# Switch_de_potencia.net
KiCad netlist of a schematic drawn in EAGLE
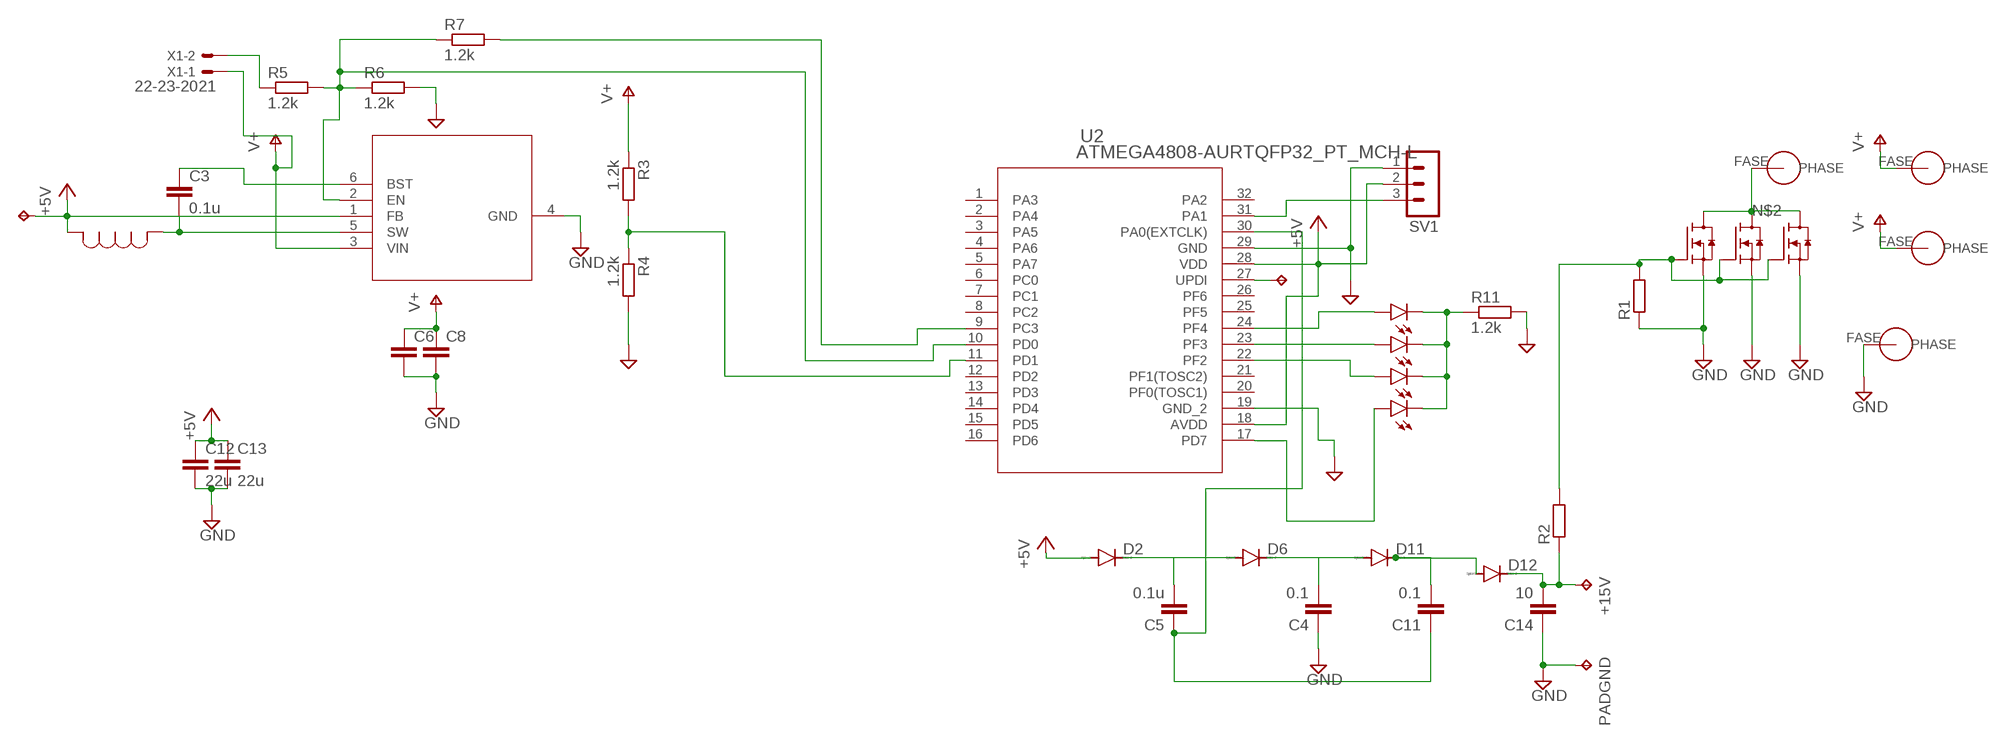
[diagram p0: schematic, sheet 1]

(export (version "E")
  (design (tool "Eeschema 10.0.6"))
  (components
    (comp (ref "+15V")
      (value "TPB1,27")
      (footprint "eagle-import:B1,27")
      (libsource (lib "eagle-import") (part "TPB1,27"))
    )
    (comp (ref "C3")
      (value "0.1u")
      (footprint "eagle-import:C0402")
      (libsource (lib "eagle-import") (part "C-EUC0402"))
    )
    (comp (ref "C4")
      (value "0.1")
      (footprint "eagle-import:C0805")
      (libsource (lib "eagle-import") (part "C-EUC0805"))
    )
    (comp (ref "C5")
      (value "0.1u")
      (footprint "eagle-import:C0805")
      (libsource (lib "eagle-import") (part "C-EUC0805"))
    )
    (comp (ref "C6")
      (value "C-EUC0805")
      (footprint "eagle-import:C0805")
      (libsource (lib "eagle-import") (part "C-EUC0805"))
    )
    (comp (ref "C8")
      (value "C-EUC0805")
      (footprint "eagle-import:C0805")
      (libsource (lib "eagle-import") (part "C-EUC0805"))
    )
    (comp (ref "C11")
      (value "0.1")
      (footprint "eagle-import:C0805")
      (libsource (lib "eagle-import") (part "C-EUC0805"))
    )
    (comp (ref "C12")
      (value "22u")
      (footprint "eagle-import:C0402")
      (libsource (lib "eagle-import") (part "C-EUC0402"))
    )
    (comp (ref "C13")
      (value "22u")
      (footprint "eagle-import:C0402")
      (libsource (lib "eagle-import") (part "C-EUC0402"))
    )
    (comp (ref "C14")
      (value "10")
      (footprint "eagle-import:C0805")
      (libsource (lib "eagle-import") (part "C-EUC0805"))
    )
    (comp (ref "D2")
      (value "DIODE-MINIMELF")
      (footprint "eagle-import:MINIMELF")
      (libsource (lib "eagle-import") (part "DIODE-MINIMELF"))
    )
    (comp (ref "D6")
      (value "DIODE-MINIMELF")
      (footprint "eagle-import:MINIMELF")
      (libsource (lib "eagle-import") (part "DIODE-MINIMELF"))
    )
    (comp (ref "D11")
      (value "DIODE-MINIMELF")
      (footprint "eagle-import:MINIMELF")
      (libsource (lib "eagle-import") (part "DIODE-MINIMELF"))
    )
    (comp (ref "D12")
      (value "DIODE-MINIMELF")
      (footprint "eagle-import:MINIMELF")
      (libsource (lib "eagle-import") (part "DIODE-MINIMELF"))
    )
    (comp (ref "GND")
      (value "PHASE")
      (footprint "eagle-import:POWEROUT")
      (libsource (lib "eagle-import") (part "PHASE"))
    )
    (comp (ref "LA1")
      (value "IPB180N06S4-H1")
      (footprint "eagle-import:PG-TO263-7-3")
      (libsource (lib "eagle-import") (part "IPB180N06S4-H1"))
    )
    (comp (ref "LA2")
      (value "IPB180N06S4-H1")
      (footprint "eagle-import:PG-TO263-7-3")
      (libsource (lib "eagle-import") (part "IPB180N06S4-H1"))
    )
    (comp (ref "LA3")
      (value "IPB180N06S4-H1")
      (footprint "eagle-import:PG-TO263-7-3")
      (libsource (lib "eagle-import") (part "IPB180N06S4-H1"))
    )
    (comp (ref "OUTPUT")
      (value "PHASE")
      (footprint "eagle-import:POWEROUT")
      (libsource (lib "eagle-import") (part "PHASE"))
    )
    (comp (ref "PADGND")
      (value "TPB1,27")
      (footprint "eagle-import:B1,27")
      (libsource (lib "eagle-import") (part "TPB1,27"))
    )
    (comp (ref "POWERON2")
      (value "LEDCHIPLED_0603")
      (footprint "eagle-import:CHIPLED_0603")
      (libsource (lib "eagle-import") (part "LEDCHIPLED_0603"))
    )
    (comp (ref "POWERON3")
      (value "LEDCHIPLED_0603")
      (footprint "eagle-import:CHIPLED_0603")
      (libsource (lib "eagle-import") (part "LEDCHIPLED_0603"))
    )
    (comp (ref "POWERON4")
      (value "LEDCHIPLED_0603")
      (footprint "eagle-import:CHIPLED_0603")
      (libsource (lib "eagle-import") (part "LEDCHIPLED_0603"))
    )
    (comp (ref "POWERON5")
      (value "LEDCHIPLED_0603")
      (footprint "eagle-import:CHIPLED_0603")
      (libsource (lib "eagle-import") (part "LEDCHIPLED_0603"))
    )
    (comp (ref "R1")
      (value "R-EU_R0603")
      (footprint "eagle-import:R0603")
      (libsource (lib "eagle-import") (part "R-EU_R0603"))
    )
    (comp (ref "R2")
      (value "R-EU_R0603")
      (footprint "eagle-import:R0603")
      (libsource (lib "eagle-import") (part "R-EU_R0603"))
    )
    (comp (ref "R3")
      (value "1.2k")
      (footprint "eagle-import:M0805")
      (libsource (lib "eagle-import") (part "R-EU_M0805"))
    )
    (comp (ref "R4")
      (value "1.2k")
      (footprint "eagle-import:M0805")
      (libsource (lib "eagle-import") (part "R-EU_M0805"))
    )
    (comp (ref "R5")
      (value "1.2k")
      (footprint "eagle-import:M0805")
      (libsource (lib "eagle-import") (part "R-EU_M0805"))
    )
    (comp (ref "R6")
      (value "1.2k")
      (footprint "eagle-import:M0805")
      (libsource (lib "eagle-import") (part "R-EU_M0805"))
    )
    (comp (ref "R7")
      (value "1.2k")
      (footprint "eagle-import:M0805")
      (libsource (lib "eagle-import") (part "R-EU_M0805"))
    )
    (comp (ref "R11")
      (value "1.2k")
      (footprint "eagle-import:M0805")
      (libsource (lib "eagle-import") (part "R-EU_M0805"))
    )
    (comp (ref "SV1")
      (value "MA03-1")
      (footprint "eagle-import:MA03-1")
      (libsource (lib "eagle-import") (part "MA03-1"))
    )
    (comp (ref "TP1")
      (value "TPB1,27")
      (footprint "eagle-import:B1,27")
      (libsource (lib "eagle-import") (part "TPB1,27"))
    )
    (comp (ref "TP9")
      (value "TPB1,27")
      (footprint "eagle-import:B1,27")
      (libsource (lib "eagle-import") (part "TPB1,27"))
    )
    (comp (ref "U$1")
      (value "INDUCTOR4.7")
      (footprint "eagle-import:IND_NRS5030T100MMGJ_TAY")
      (libsource (lib "eagle-import") (part "INDUCTOR4.7"))
    )
    (comp (ref "U2")
      (value "ATMEGA4808-AURTQFP32_PT_MCH-L")
      (footprint "eagle-import:TQFP32_PT_MCH-L")
      (fields
        (field (name "MANUFACTURER_PART_NUMBER") "ATMEGA4808-AUR")
        (field (name "COPYRIGHT") "Copyright (C) 2018 Accelerated Designs. All rights reserved")
      )
      (libsource (lib "eagle-import") (part "ATMEGA4808-AURTQFP32_PT_MCH-L"))
    )
    (comp (ref "U3")
      (value "AP63205WU-7SOIC_05WU-7_DIO-M")
      (footprint "eagle-import:SOIC_05WU-7_DIO-M")
      (fields
        (field (name "MANUFACTURER_PART_NUMBER") "AP63205WU-7")
        (field (name "COPYRIGHT") "Copyright (C) 2018 Accelerated Designs. All rights reserved")
      )
      (libsource (lib "eagle-import") (part "AP63205WU-7SOIC_05WU-7_DIO-M"))
    )
    (comp (ref "V+")
      (value "PHASE")
      (footprint "eagle-import:POWEROUT")
      (libsource (lib "eagle-import") (part "PHASE"))
    )
    (comp (ref "V+1")
      (value "PHASE")
      (footprint "eagle-import:POWEROUT")
      (libsource (lib "eagle-import") (part "PHASE"))
    )
    (comp (ref "X1")
      (value "22-23-2021")
      (footprint "eagle-import:22-23-2021")
      (fields (field (name "MF") "MOLEX"))
      (libsource (lib "eagle-import") (part "22-23-2021"))
    )
  )
  (nets
    (net (code "1") (name "+5V") (class "Default")
      (node (ref "C12") (pin "1") (pinfunction "1_1") (pintype "passive"))
      (node (ref "C13") (pin "1") (pinfunction "1_1") (pintype "passive"))
      (node (ref "D2") (pin "A") (pinfunction "A_A") (pintype "passive"))
      (node (ref "SV1") (pin "2") (pinfunction "2_2") (pintype "passive"))
      (node (ref "TP9") (pin "TP") (pinfunction "TP_TP") (pintype "input"))
      (node (ref "U$1") (pin "1") (pinfunction "1_1") (pintype "passive"))
      (node (ref "U2") (pin "18") (pinfunction "AVDD_18") (pintype "power_in"))
      (node (ref "U2") (pin "28") (pinfunction "VDD_28") (pintype "power_in"))
      (node (ref "U3") (pin "1") (pinfunction "FB_1") (pintype "passive"))
    )
    (net (code "2") (name "/N$2") (class "Default")
      (node (ref "LA1") (pin "8") (pinfunction "D_8") (pintype "passive"))
      (node (ref "LA2") (pin "8") (pinfunction "D_8") (pintype "passive"))
      (node (ref "LA3") (pin "8") (pinfunction "D_8") (pintype "passive"))
      (node (ref "OUTPUT") (pin "FASE") (pinfunction "PHASE_FASE") (pintype "bidirectional"))
    )
    (net (code "3") (name "GND") (class "Default")
      (node (ref "C12") (pin "2") (pinfunction "2_2") (pintype "passive"))
      (node (ref "C13") (pin "2") (pinfunction "2_2") (pintype "passive"))
      (node (ref "C14") (pin "1") (pinfunction "1_1") (pintype "passive"))
      (node (ref "C4") (pin "1") (pinfunction "1_1") (pintype "passive"))
      (node (ref "C6") (pin "2") (pinfunction "2_2") (pintype "passive"))
      (node (ref "C8") (pin "2") (pinfunction "2_2") (pintype "passive"))
      (node (ref "GND") (pin "FASE") (pinfunction "PHASE_FASE") (pintype "bidirectional"))
      (node (ref "LA1") (pin "2") (pinfunction "S_2") (pintype "passive"))
      (node (ref "LA1") (pin "3") (pinfunction "S_3") (pintype "passive"))
      (node (ref "LA1") (pin "5") (pinfunction "S_5") (pintype "passive"))
      (node (ref "LA1") (pin "6") (pinfunction "S_6") (pintype "passive"))
      (node (ref "LA1") (pin "7") (pinfunction "S_7") (pintype "passive"))
      (node (ref "LA2") (pin "2") (pinfunction "S_2") (pintype "passive"))
      (node (ref "LA2") (pin "3") (pinfunction "S_3") (pintype "passive"))
      (node (ref "LA2") (pin "5") (pinfunction "S_5") (pintype "passive"))
      (node (ref "LA2") (pin "6") (pinfunction "S_6") (pintype "passive"))
      (node (ref "LA2") (pin "7") (pinfunction "S_7") (pintype "passive"))
      (node (ref "LA3") (pin "2") (pinfunction "S_2") (pintype "passive"))
      (node (ref "LA3") (pin "3") (pinfunction "S_3") (pintype "passive"))
      (node (ref "LA3") (pin "5") (pinfunction "S_5") (pintype "passive"))
      (node (ref "LA3") (pin "6") (pinfunction "S_6") (pintype "passive"))
      (node (ref "LA3") (pin "7") (pinfunction "S_7") (pintype "passive"))
      (node (ref "PADGND") (pin "TP") (pinfunction "TP_TP") (pintype "input"))
      (node (ref "R1") (pin "1") (pinfunction "1_1") (pintype "passive"))
      (node (ref "R11") (pin "2") (pinfunction "2_2") (pintype "passive"))
      (node (ref "R4") (pin "2") (pinfunction "2_2") (pintype "passive"))
      (node (ref "R6") (pin "2") (pinfunction "2_2") (pintype "passive"))
      (node (ref "SV1") (pin "1") (pinfunction "1_1") (pintype "passive"))
      (node (ref "U2") (pin "19") (pinfunction "GND_2_19") (pintype "passive"))
      (node (ref "U2") (pin "29") (pinfunction "GND_29") (pintype "passive"))
      (node (ref "U3") (pin "4") (pinfunction "GND_4") (pintype "passive"))
    )
    (net (code "4") (name "Net-(+15V-PadTP)") (class "Default")
      (node (ref "+15V") (pin "TP") (pinfunction "TP_TP") (pintype "input"))
      (node (ref "C14") (pin "2") (pinfunction "2_2") (pintype "passive"))
      (node (ref "D12") (pin "C") (pinfunction "C_C") (pintype "passive"))
      (node (ref "R2") (pin "1") (pinfunction "1_1") (pintype "passive"))
    )
    (net (code "5") (name "Net-(C4-Pad2)") (class "Default")
      (node (ref "C4") (pin "2") (pinfunction "2_2") (pintype "passive"))
      (node (ref "D11") (pin "A") (pinfunction "A_A") (pintype "passive"))
      (node (ref "D6") (pin "C") (pinfunction "C_C") (pintype "passive"))
    )
    (net (code "6") (name "Net-(C5-Pad2)") (class "Default")
      (node (ref "C5") (pin "2") (pinfunction "2_2") (pintype "passive"))
      (node (ref "D2") (pin "C") (pinfunction "C_C") (pintype "passive"))
      (node (ref "D6") (pin "A") (pinfunction "A_A") (pintype "passive"))
    )
    (net (code "7") (name "Net-(C11-Pad2)") (class "Default")
      (node (ref "C11") (pin "2") (pinfunction "2_2") (pintype "passive"))
      (node (ref "D11") (pin "C") (pinfunction "C_C") (pintype "passive"))
      (node (ref "D12") (pin "A") (pinfunction "A_A") (pintype "passive"))
    )
    (net (code "8") (name "Net-(LA1-G)") (class "Default")
      (node (ref "LA1") (pin "1") (pinfunction "G_1") (pintype "passive"))
      (node (ref "LA2") (pin "1") (pinfunction "G_1") (pintype "passive"))
      (node (ref "LA3") (pin "1") (pinfunction "G_1") (pintype "passive"))
      (node (ref "R1") (pin "2") (pinfunction "2_2") (pintype "passive"))
      (node (ref "R2") (pin "2") (pinfunction "2_2") (pintype "passive"))
    )
    (net (code "9") (name "Net-(POWERON2-PadC)") (class "Default")
      (node (ref "POWERON2") (pin "C") (pinfunction "C_C") (pintype "passive"))
      (node (ref "POWERON3") (pin "C") (pinfunction "C_C") (pintype "passive"))
      (node (ref "POWERON4") (pin "C") (pinfunction "C_C") (pintype "passive"))
      (node (ref "POWERON5") (pin "C") (pinfunction "C_C") (pintype "passive"))
      (node (ref "R11") (pin "1") (pinfunction "1_1") (pintype "passive"))
    )
    (net (code "10") (name "Net-(U2-PA0(EXTCLK))") (class "Default")
      (node (ref "C11") (pin "1") (pinfunction "1_1") (pintype "passive"))
      (node (ref "C5") (pin "1") (pinfunction "1_1") (pintype "passive"))
      (node (ref "U2") (pin "30") (pinfunction "PA0(EXTCLK)_30") (pintype "bidirectional"))
    )
    (net (code "11") (name "Net-(U2-PA1)") (class "Default")
      (node (ref "SV1") (pin "3") (pinfunction "3_3") (pintype "passive"))
      (node (ref "U2") (pin "31") (pinfunction "PA1_31") (pintype "bidirectional"))
    )
    (net (code "12") (name "Net-(U2-PC3)") (class "Default")
      (node (ref "R7") (pin "2") (pinfunction "2_2") (pintype "passive"))
      (node (ref "U2") (pin "9") (pinfunction "PC3_9") (pintype "bidirectional"))
    )
    (net (code "13") (name "Net-(U2-PD0)") (class "Default")
      (node (ref "R5") (pin "2") (pinfunction "2_2") (pintype "passive"))
      (node (ref "R6") (pin "1") (pinfunction "1_1") (pintype "passive"))
      (node (ref "R7") (pin "1") (pinfunction "1_1") (pintype "passive"))
      (node (ref "U2") (pin "10") (pinfunction "PD0_10") (pintype "bidirectional"))
      (node (ref "U3") (pin "2") (pinfunction "EN_2") (pintype "passive"))
    )
    (net (code "14") (name "Net-(U2-PD1)") (class "Default")
      (node (ref "R3") (pin "2") (pinfunction "2_2") (pintype "passive"))
      (node (ref "R4") (pin "1") (pinfunction "1_1") (pintype "passive"))
      (node (ref "U2") (pin "11") (pinfunction "PD1_11") (pintype "bidirectional"))
    )
    (net (code "15") (name "Net-(U2-PD7)") (class "Default")
      (node (ref "POWERON4") (pin "A") (pinfunction "A_A") (pintype "passive"))
      (node (ref "U2") (pin "17") (pinfunction "PD7_17") (pintype "bidirectional"))
    )
    (net (code "16") (name "Net-(U2-PF2)") (class "Default")
      (node (ref "POWERON5") (pin "A") (pinfunction "A_A") (pintype "passive"))
      (node (ref "U2") (pin "22") (pinfunction "PF2_22") (pintype "bidirectional"))
    )
    (net (code "17") (name "Net-(U2-PF3)") (class "Default")
      (node (ref "POWERON2") (pin "A") (pinfunction "A_A") (pintype "passive"))
      (node (ref "U2") (pin "23") (pinfunction "PF3_23") (pintype "bidirectional"))
    )
    (net (code "18") (name "Net-(U2-PF4)") (class "Default")
      (node (ref "POWERON3") (pin "A") (pinfunction "A_A") (pintype "passive"))
      (node (ref "U2") (pin "24") (pinfunction "PF4_24") (pintype "bidirectional"))
    )
    (net (code "19") (name "Net-(U2-UPDI)") (class "Default")
      (node (ref "TP1") (pin "TP") (pinfunction "TP_TP") (pintype "input"))
      (node (ref "U2") (pin "27") (pinfunction "UPDI_27") (pintype "bidirectional"))
    )
    (net (code "20") (name "Net-(U3-BST)") (class "Default")
      (node (ref "C3") (pin "1") (pinfunction "1_1") (pintype "passive"))
      (node (ref "U3") (pin "6") (pinfunction "BST_6") (pintype "passive"))
    )
    (net (code "21") (name "Net-(U3-SW)") (class "Default")
      (node (ref "C3") (pin "2") (pinfunction "2_2") (pintype "passive"))
      (node (ref "U$1") (pin "2") (pinfunction "2_2") (pintype "passive"))
      (node (ref "U3") (pin "5") (pinfunction "SW_5") (pintype "passive"))
    )
    (net (code "22") (name "Net-(X1B-S)") (class "Default")
      (node (ref "R5") (pin "1") (pinfunction "1_1") (pintype "passive"))
      (node (ref "X1") (pin "2") (pinfunction "S_2") (pintype "passive"))
    )
    (net (code "23") (name "V+") (class "Default")
      (node (ref "C6") (pin "1") (pinfunction "1_1") (pintype "passive"))
      (node (ref "C8") (pin "1") (pinfunction "1_1") (pintype "passive"))
      (node (ref "R3") (pin "1") (pinfunction "1_1") (pintype "passive"))
      (node (ref "U3") (pin "3") (pinfunction "VIN_3") (pintype "passive"))
      (node (ref "V+") (pin "FASE") (pinfunction "PHASE_FASE") (pintype "bidirectional"))
      (node (ref "V+1") (pin "FASE") (pinfunction "PHASE_FASE") (pintype "bidirectional"))
      (node (ref "X1") (pin "1") (pinfunction "S_1") (pintype "passive"))
    )
    (net (code "24") (name "unconnected-(U2-PA2-Pad32)") (class "Default")
      (node (ref "U2") (pin "32") (pinfunction "PA2_32") (pintype "bidirectional"))
    )
    (net (code "25") (name "unconnected-(U2-PA3-Pad1)") (class "Default")
      (node (ref "U2") (pin "1") (pinfunction "PA3_1") (pintype "bidirectional"))
    )
    (net (code "26") (name "unconnected-(U2-PA4-Pad2)") (class "Default")
      (node (ref "U2") (pin "2") (pinfunction "PA4_2") (pintype "bidirectional"))
    )
    (net (code "27") (name "unconnected-(U2-PA5-Pad3)") (class "Default")
      (node (ref "U2") (pin "3") (pinfunction "PA5_3") (pintype "bidirectional"))
    )
    (net (code "28") (name "unconnected-(U2-PA6-Pad4)") (class "Default")
      (node (ref "U2") (pin "4") (pinfunction "PA6_4") (pintype "bidirectional"))
    )
    (net (code "29") (name "unconnected-(U2-PA7-Pad5)") (class "Default")
      (node (ref "U2") (pin "5") (pinfunction "PA7_5") (pintype "bidirectional"))
    )
    (net (code "30") (name "unconnected-(U2-PC0-Pad6)") (class "Default")
      (node (ref "U2") (pin "6") (pinfunction "PC0_6") (pintype "bidirectional"))
    )
    (net (code "31") (name "unconnected-(U2-PC1-Pad7)") (class "Default")
      (node (ref "U2") (pin "7") (pinfunction "PC1_7") (pintype "bidirectional"))
    )
    (net (code "32") (name "unconnected-(U2-PC2-Pad8)") (class "Default")
      (node (ref "U2") (pin "8") (pinfunction "PC2_8") (pintype "bidirectional"))
    )
    (net (code "33") (name "unconnected-(U2-PD2-Pad12)") (class "Default")
      (node (ref "U2") (pin "12") (pinfunction "PD2_12") (pintype "bidirectional"))
    )
    (net (code "34") (name "unconnected-(U2-PD3-Pad13)") (class "Default")
      (node (ref "U2") (pin "13") (pinfunction "PD3_13") (pintype "bidirectional"))
    )
    (net (code "35") (name "unconnected-(U2-PD4-Pad14)") (class "Default")
      (node (ref "U2") (pin "14") (pinfunction "PD4_14") (pintype "bidirectional"))
    )
    (net (code "36") (name "unconnected-(U2-PD5-Pad15)") (class "Default")
      (node (ref "U2") (pin "15") (pinfunction "PD5_15") (pintype "bidirectional"))
    )
    (net (code "37") (name "unconnected-(U2-PD6-Pad16)") (class "Default")
      (node (ref "U2") (pin "16") (pinfunction "PD6_16") (pintype "bidirectional"))
    )
    (net (code "38") (name "unconnected-(U2-PF0(TOSC1)-Pad20)") (class "Default")
      (node (ref "U2") (pin "20") (pinfunction "PF0(TOSC1)_20") (pintype "bidirectional"))
    )
    (net (code "39") (name "unconnected-(U2-PF1(TOSC2)-Pad21)") (class "Default")
      (node (ref "U2") (pin "21") (pinfunction "PF1(TOSC2)_21") (pintype "bidirectional"))
    )
    (net (code "40") (name "unconnected-(U2-PF5-Pad25)") (class "Default")
      (node (ref "U2") (pin "25") (pinfunction "PF5_25") (pintype "bidirectional"))
    )
    (net (code "41") (name "unconnected-(U2-PF6-Pad26)") (class "Default")
      (node (ref "U2") (pin "26") (pinfunction "PF6_26") (pintype "bidirectional"))
    )
  )
)
